# pandemic-v0001.net
KiCad netlist of a schematic drawn in EAGLE
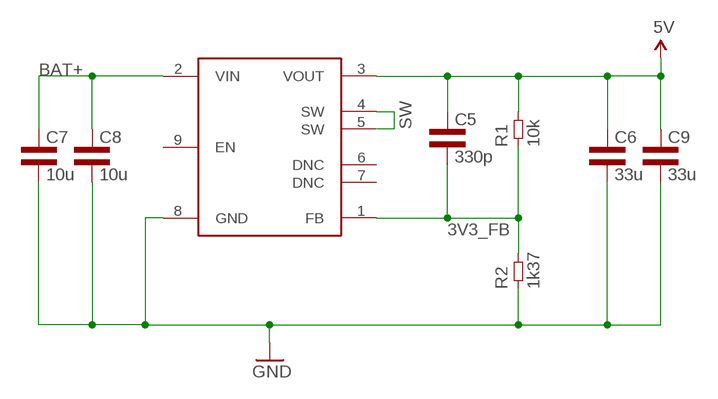
[diagram p0: schematic, sheet 1]
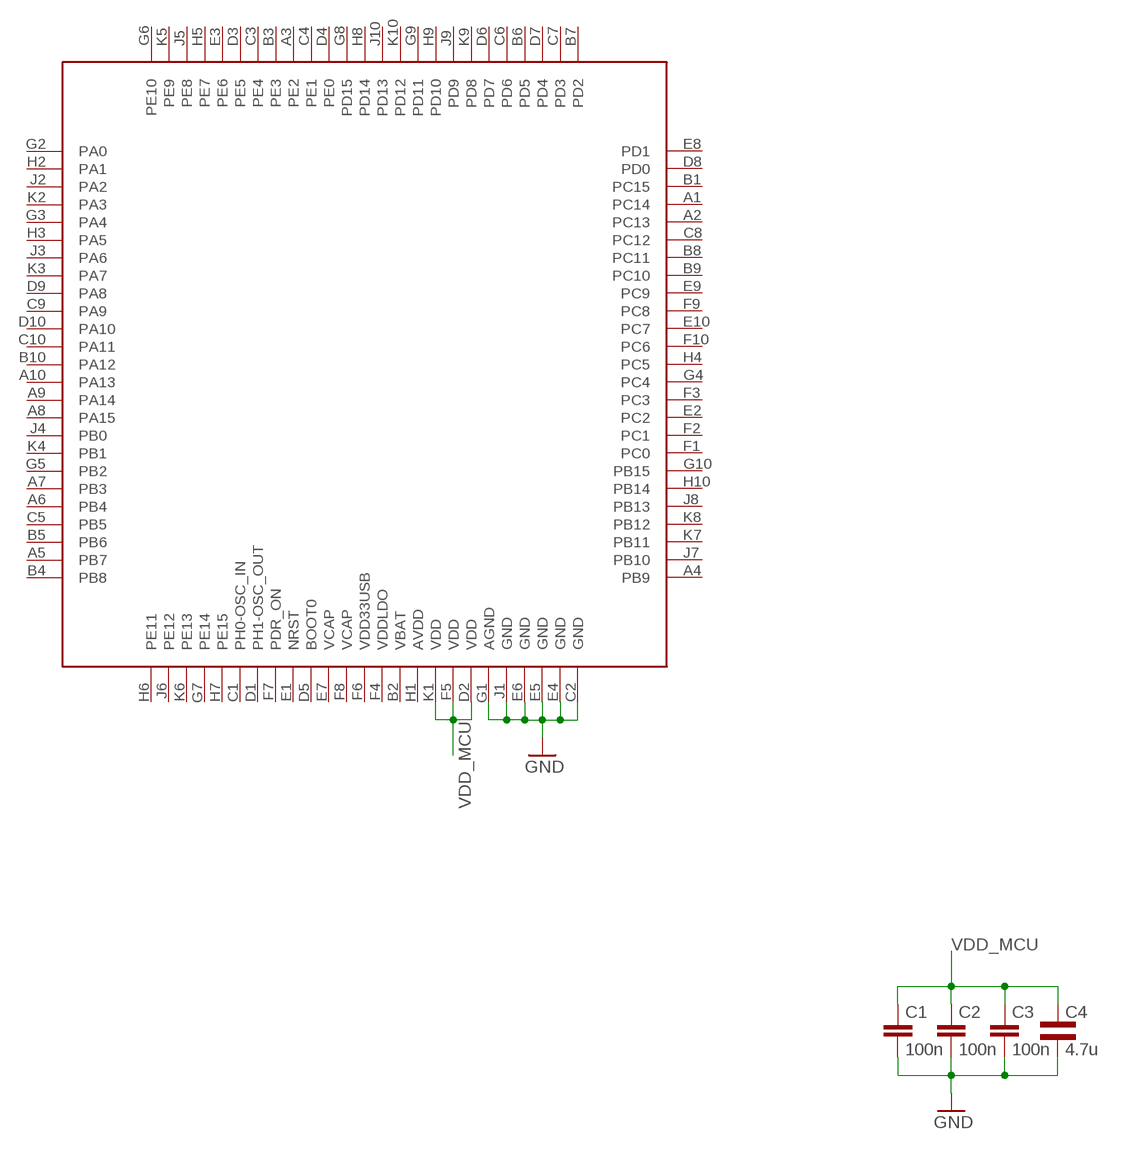
[diagram p1: schematic, sheet 2]

(export (version "E")
  (design (tool "Eeschema 10.0.6"))
  (components
    (comp (ref "C1")
      (value "100n")
      (footprint "eagle-import:C0201")
      (libsource (lib "eagle-import") (part "C-EUC0201"))
    )
    (comp (ref "C2")
      (value "100n")
      (footprint "eagle-import:C0201")
      (libsource (lib "eagle-import") (part "C-EUC0201"))
    )
    (comp (ref "C3")
      (value "100n")
      (footprint "eagle-import:C0201")
      (libsource (lib "eagle-import") (part "C-EUC0201"))
    )
    (comp (ref "C4")
      (value "4.7u")
      (footprint "eagle-import:0805L3")
      (libsource (lib "eagle-import") (part "CAP0805L3"))
    )
    (comp (ref "U1")
      (value "STM32H743VIH")
      (footprint "eagle-import:BGA100C80P10X10_800X800X110")
      (libsource (lib "eagle-import") (part "STM32H743VIH"))
    )
    (comp (ref "C5")
      (value "330p")
      (footprint "eagle-import:0402L3")
      (libsource (lib "eagle-import") (part "CAP0402L3"))
    )
    (comp (ref "C6")
      (value "33u")
      (footprint "eagle-import:1210L3")
      (libsource (lib "eagle-import") (part "CAP1210L3"))
    )
    (comp (ref "C7")
      (value "10u")
      (footprint "eagle-import:1210L3")
      (libsource (lib "eagle-import") (part "CAP1210L3"))
    )
    (comp (ref "C8")
      (value "10u")
      (footprint "eagle-import:1210L3")
      (libsource (lib "eagle-import") (part "CAP1210L3"))
    )
    (comp (ref "C9")
      (value "33u")
      (footprint "eagle-import:1210L3")
      (libsource (lib "eagle-import") (part "CAP1210L3"))
    )
    (comp (ref "R1")
      (value "10k")
      (footprint "eagle-import:0402L3")
      (libsource (lib "eagle-import") (part "RES0402L3"))
    )
    (comp (ref "R2")
      (value "1k37")
      (footprint "eagle-import:0402L3")
      (libsource (lib "eagle-import") (part "RES0402L3"))
    )
    (comp (ref "U2")
      (value "TPSM84209RKH")
      (footprint "eagle-import:TPSM84209RKHT")
      (libsource (lib "eagle-import") (part "TPSM84209RKH"))
    )
  )
  (nets
    (net (code "1") (name "3V3_FB") (class "Default")
      (node (ref "C5") (pin "P$2") (pinfunction "2_P$2") (pintype "bidirectional"))
      (node (ref "R1") (pin "P$1") (pinfunction "1_P$1") (pintype "bidirectional"))
      (node (ref "R2") (pin "P$2") (pinfunction "2_P$2") (pintype "bidirectional"))
      (node (ref "U2") (pin "1") (pinfunction "FB_1") (pintype "bidirectional"))
    )
    (net (code "2") (name "5V") (class "Default")
      (node (ref "C5") (pin "P$1") (pinfunction "1_P$1") (pintype "bidirectional"))
      (node (ref "C6") (pin "P$1") (pinfunction "1_P$1") (pintype "bidirectional"))
      (node (ref "C9") (pin "P$1") (pinfunction "1_P$1") (pintype "bidirectional"))
      (node (ref "R1") (pin "P$2") (pinfunction "2_P$2") (pintype "bidirectional"))
      (node (ref "U2") (pin "3") (pinfunction "VOUT_3") (pintype "bidirectional"))
    )
    (net (code "3") (name "BAT+") (class "Default")
      (node (ref "C7") (pin "P$1") (pinfunction "1_P$1") (pintype "bidirectional"))
      (node (ref "C8") (pin "P$1") (pinfunction "1_P$1") (pintype "bidirectional"))
      (node (ref "U2") (pin "2") (pinfunction "VIN_2") (pintype "bidirectional"))
    )
    (net (code "4") (name "GND") (class "Default")
      (node (ref "C1") (pin "2") (pinfunction "2_2") (pintype "passive"))
      (node (ref "C2") (pin "2") (pinfunction "2_2") (pintype "passive"))
      (node (ref "C3") (pin "2") (pinfunction "2_2") (pintype "passive"))
      (node (ref "C4") (pin "2") (pinfunction "2_2") (pintype "bidirectional"))
      (node (ref "C6") (pin "P$2") (pinfunction "2_P$2") (pintype "bidirectional"))
      (node (ref "C7") (pin "P$2") (pinfunction "2_P$2") (pintype "bidirectional"))
      (node (ref "C8") (pin "P$2") (pinfunction "2_P$2") (pintype "bidirectional"))
      (node (ref "C9") (pin "P$2") (pinfunction "2_P$2") (pintype "bidirectional"))
      (node (ref "R2") (pin "P$1") (pinfunction "1_P$1") (pintype "bidirectional"))
      (node (ref "U1") (pin "C2") (pinfunction "GND_C2") (pintype "bidirectional"))
      (node (ref "U1") (pin "E4") (pinfunction "GND_E4") (pintype "bidirectional"))
      (node (ref "U1") (pin "E5") (pinfunction "GND_E5") (pintype "bidirectional"))
      (node (ref "U1") (pin "E6") (pinfunction "GND_E6") (pintype "bidirectional"))
      (node (ref "U1") (pin "G1") (pinfunction "AGND_G1") (pintype "bidirectional"))
      (node (ref "U1") (pin "J1") (pinfunction "GND_J1") (pintype "bidirectional"))
      (node (ref "U2") (pin "8") (pinfunction "GND_8") (pintype "bidirectional"))
    )
    (net (code "5") (name "SW") (class "Default")
      (node (ref "U2") (pin "4") (pinfunction "SW_4") (pintype "bidirectional"))
      (node (ref "U2") (pin "5") (pinfunction "SW_5") (pintype "bidirectional"))
    )
    (net (code "6") (name "VDD_MCU") (class "Default")
      (node (ref "C1") (pin "1") (pinfunction "1_1") (pintype "passive"))
      (node (ref "C2") (pin "1") (pinfunction "1_1") (pintype "passive"))
      (node (ref "C3") (pin "1") (pinfunction "1_1") (pintype "passive"))
      (node (ref "C4") (pin "1") (pinfunction "1_1") (pintype "bidirectional"))
      (node (ref "U1") (pin "D2") (pinfunction "VDD_D2") (pintype "bidirectional"))
      (node (ref "U1") (pin "F5") (pinfunction "VDD_F5") (pintype "bidirectional"))
      (node (ref "U1") (pin "K1") (pinfunction "VDD_K1") (pintype "bidirectional"))
    )
    (net (code "7") (name "unconnected-(U1-AVDD-PadH1)") (class "Default")
      (node (ref "U1") (pin "H1") (pinfunction "AVDD_H1") (pintype "bidirectional"))
    )
    (net (code "8") (name "unconnected-(U1-BOOT0-PadD5)") (class "Default")
      (node (ref "U1") (pin "D5") (pinfunction "BOOT0_D5") (pintype "bidirectional"))
    )
    (net (code "9") (name "unconnected-(U1-NRST-PadE1)") (class "Default")
      (node (ref "U1") (pin "E1") (pinfunction "NRST_E1") (pintype "bidirectional"))
    )
    (net (code "10") (name "unconnected-(U1-PA0-PadG2)") (class "Default")
      (node (ref "U1") (pin "G2") (pinfunction "PA0_G2") (pintype "bidirectional"))
    )
    (net (code "11") (name "unconnected-(U1-PA1-PadH2)") (class "Default")
      (node (ref "U1") (pin "H2") (pinfunction "PA1_H2") (pintype "bidirectional"))
    )
    (net (code "12") (name "unconnected-(U1-PA2-PadJ2)") (class "Default")
      (node (ref "U1") (pin "J2") (pinfunction "PA2_J2") (pintype "bidirectional"))
    )
    (net (code "13") (name "unconnected-(U1-PA3-PadK2)") (class "Default")
      (node (ref "U1") (pin "K2") (pinfunction "PA3_K2") (pintype "bidirectional"))
    )
    (net (code "14") (name "unconnected-(U1-PA4-PadG3)") (class "Default")
      (node (ref "U1") (pin "G3") (pinfunction "PA4_G3") (pintype "bidirectional"))
    )
    (net (code "15") (name "unconnected-(U1-PA5-PadH3)") (class "Default")
      (node (ref "U1") (pin "H3") (pinfunction "PA5_H3") (pintype "bidirectional"))
    )
    (net (code "16") (name "unconnected-(U1-PA6-PadJ3)") (class "Default")
      (node (ref "U1") (pin "J3") (pinfunction "PA6_J3") (pintype "bidirectional"))
    )
    (net (code "17") (name "unconnected-(U1-PA7-PadK3)") (class "Default")
      (node (ref "U1") (pin "K3") (pinfunction "PA7_K3") (pintype "bidirectional"))
    )
    (net (code "18") (name "unconnected-(U1-PA8-PadD9)") (class "Default")
      (node (ref "U1") (pin "D9") (pinfunction "PA8_D9") (pintype "bidirectional"))
    )
    (net (code "19") (name "unconnected-(U1-PA9-PadC9)") (class "Default")
      (node (ref "U1") (pin "C9") (pinfunction "PA9_C9") (pintype "bidirectional"))
    )
    (net (code "20") (name "unconnected-(U1-PA10-PadD10)") (class "Default")
      (node (ref "U1") (pin "D10") (pinfunction "PA10_D10") (pintype "bidirectional"))
    )
    (net (code "21") (name "unconnected-(U1-PA11-PadC10)") (class "Default")
      (node (ref "U1") (pin "C10") (pinfunction "PA11_C10") (pintype "bidirectional"))
    )
    (net (code "22") (name "unconnected-(U1-PA12-PadB10)") (class "Default")
      (node (ref "U1") (pin "B10") (pinfunction "PA12_B10") (pintype "bidirectional"))
    )
    (net (code "23") (name "unconnected-(U1-PA13-PadA10)") (class "Default")
      (node (ref "U1") (pin "A10") (pinfunction "PA13_A10") (pintype "bidirectional"))
    )
    (net (code "24") (name "unconnected-(U1-PA14-PadA9)") (class "Default")
      (node (ref "U1") (pin "A9") (pinfunction "PA14_A9") (pintype "bidirectional"))
    )
    (net (code "25") (name "unconnected-(U1-PA15-PadA8)") (class "Default")
      (node (ref "U1") (pin "A8") (pinfunction "PA15_A8") (pintype "bidirectional"))
    )
    (net (code "26") (name "unconnected-(U1-PB0-PadJ4)") (class "Default")
      (node (ref "U1") (pin "J4") (pinfunction "PB0_J4") (pintype "bidirectional"))
    )
    (net (code "27") (name "unconnected-(U1-PB1-PadK4)") (class "Default")
      (node (ref "U1") (pin "K4") (pinfunction "PB1_K4") (pintype "bidirectional"))
    )
    (net (code "28") (name "unconnected-(U1-PB2-PadG5)") (class "Default")
      (node (ref "U1") (pin "G5") (pinfunction "PB2_G5") (pintype "bidirectional"))
    )
    (net (code "29") (name "unconnected-(U1-PB3-PadA7)") (class "Default")
      (node (ref "U1") (pin "A7") (pinfunction "PB3_A7") (pintype "bidirectional"))
    )
    (net (code "30") (name "unconnected-(U1-PB4-PadA6)") (class "Default")
      (node (ref "U1") (pin "A6") (pinfunction "PB4_A6") (pintype "bidirectional"))
    )
    (net (code "31") (name "unconnected-(U1-PB5-PadC5)") (class "Default")
      (node (ref "U1") (pin "C5") (pinfunction "PB5_C5") (pintype "bidirectional"))
    )
    (net (code "32") (name "unconnected-(U1-PB6-PadB5)") (class "Default")
      (node (ref "U1") (pin "B5") (pinfunction "PB6_B5") (pintype "bidirectional"))
    )
    (net (code "33") (name "unconnected-(U1-PB7-PadA5)") (class "Default")
      (node (ref "U1") (pin "A5") (pinfunction "PB7_A5") (pintype "bidirectional"))
    )
    (net (code "34") (name "unconnected-(U1-PB8-PadB4)") (class "Default")
      (node (ref "U1") (pin "B4") (pinfunction "PB8_B4") (pintype "bidirectional"))
    )
    (net (code "35") (name "unconnected-(U1-PB9-PadA4)") (class "Default")
      (node (ref "U1") (pin "A4") (pinfunction "PB9_A4") (pintype "bidirectional"))
    )
    (net (code "36") (name "unconnected-(U1-PB10-PadJ7)") (class "Default")
      (node (ref "U1") (pin "J7") (pinfunction "PB10_J7") (pintype "bidirectional"))
    )
    (net (code "37") (name "unconnected-(U1-PB11-PadK7)") (class "Default")
      (node (ref "U1") (pin "K7") (pinfunction "PB11_K7") (pintype "bidirectional"))
    )
    (net (code "38") (name "unconnected-(U1-PB12-PadK8)") (class "Default")
      (node (ref "U1") (pin "K8") (pinfunction "PB12_K8") (pintype "bidirectional"))
    )
    (net (code "39") (name "unconnected-(U1-PB13-PadJ8)") (class "Default")
      (node (ref "U1") (pin "J8") (pinfunction "PB13_J8") (pintype "bidirectional"))
    )
    (net (code "40") (name "unconnected-(U1-PB14-PadH10)") (class "Default")
      (node (ref "U1") (pin "H10") (pinfunction "PB14_H10") (pintype "bidirectional"))
    )
    (net (code "41") (name "unconnected-(U1-PB15-PadG10)") (class "Default")
      (node (ref "U1") (pin "G10") (pinfunction "PB15_G10") (pintype "bidirectional"))
    )
    (net (code "42") (name "unconnected-(U1-PC0-PadF1)") (class "Default")
      (node (ref "U1") (pin "F1") (pinfunction "PC0_F1") (pintype "bidirectional"))
    )
    (net (code "43") (name "unconnected-(U1-PC1-PadF2)") (class "Default")
      (node (ref "U1") (pin "F2") (pinfunction "PC1_F2") (pintype "bidirectional"))
    )
    (net (code "44") (name "unconnected-(U1-PC2-PadE2)") (class "Default")
      (node (ref "U1") (pin "E2") (pinfunction "PC2_E2") (pintype "bidirectional"))
    )
    (net (code "45") (name "unconnected-(U1-PC3-PadF3)") (class "Default")
      (node (ref "U1") (pin "F3") (pinfunction "PC3_F3") (pintype "bidirectional"))
    )
    (net (code "46") (name "unconnected-(U1-PC4-PadG4)") (class "Default")
      (node (ref "U1") (pin "G4") (pinfunction "PC4_G4") (pintype "bidirectional"))
    )
    (net (code "47") (name "unconnected-(U1-PC5-PadH4)") (class "Default")
      (node (ref "U1") (pin "H4") (pinfunction "PC5_H4") (pintype "bidirectional"))
    )
    (net (code "48") (name "unconnected-(U1-PC6-PadF10)") (class "Default")
      (node (ref "U1") (pin "F10") (pinfunction "PC6_F10") (pintype "bidirectional"))
    )
    (net (code "49") (name "unconnected-(U1-PC7-PadE10)") (class "Default")
      (node (ref "U1") (pin "E10") (pinfunction "PC7_E10") (pintype "bidirectional"))
    )
    (net (code "50") (name "unconnected-(U1-PC8-PadF9)") (class "Default")
      (node (ref "U1") (pin "F9") (pinfunction "PC8_F9") (pintype "bidirectional"))
    )
    (net (code "51") (name "unconnected-(U1-PC9-PadE9)") (class "Default")
      (node (ref "U1") (pin "E9") (pinfunction "PC9_E9") (pintype "bidirectional"))
    )
    (net (code "52") (name "unconnected-(U1-PC10-PadB9)") (class "Default")
      (node (ref "U1") (pin "B9") (pinfunction "PC10_B9") (pintype "bidirectional"))
    )
    (net (code "53") (name "unconnected-(U1-PC11-PadB8)") (class "Default")
      (node (ref "U1") (pin "B8") (pinfunction "PC11_B8") (pintype "bidirectional"))
    )
    (net (code "54") (name "unconnected-(U1-PC12-PadC8)") (class "Default")
      (node (ref "U1") (pin "C8") (pinfunction "PC12_C8") (pintype "bidirectional"))
    )
    (net (code "55") (name "unconnected-(U1-PC13-PadA2)") (class "Default")
      (node (ref "U1") (pin "A2") (pinfunction "PC13_A2") (pintype "bidirectional"))
    )
    (net (code "56") (name "unconnected-(U1-PC14-PadA1)") (class "Default")
      (node (ref "U1") (pin "A1") (pinfunction "PC14_A1") (pintype "bidirectional"))
    )
    (net (code "57") (name "unconnected-(U1-PC15-PadB1)") (class "Default")
      (node (ref "U1") (pin "B1") (pinfunction "PC15_B1") (pintype "bidirectional"))
    )
    (net (code "58") (name "unconnected-(U1-PD0-PadD8)") (class "Default")
      (node (ref "U1") (pin "D8") (pinfunction "PD0_D8") (pintype "bidirectional"))
    )
    (net (code "59") (name "unconnected-(U1-PD1-PadE8)") (class "Default")
      (node (ref "U1") (pin "E8") (pinfunction "PD1_E8") (pintype "bidirectional"))
    )
    (net (code "60") (name "unconnected-(U1-PD2-PadB7)") (class "Default")
      (node (ref "U1") (pin "B7") (pinfunction "PD2_B7") (pintype "bidirectional"))
    )
    (net (code "61") (name "unconnected-(U1-PD3-PadC7)") (class "Default")
      (node (ref "U1") (pin "C7") (pinfunction "PD3_C7") (pintype "bidirectional"))
    )
    (net (code "62") (name "unconnected-(U1-PD4-PadD7)") (class "Default")
      (node (ref "U1") (pin "D7") (pinfunction "PD4_D7") (pintype "bidirectional"))
    )
    (net (code "63") (name "unconnected-(U1-PD5-PadB6)") (class "Default")
      (node (ref "U1") (pin "B6") (pinfunction "PD5_B6") (pintype "bidirectional"))
    )
    (net (code "64") (name "unconnected-(U1-PD6-PadC6)") (class "Default")
      (node (ref "U1") (pin "C6") (pinfunction "PD6_C6") (pintype "bidirectional"))
    )
    (net (code "65") (name "unconnected-(U1-PD7-PadD6)") (class "Default")
      (node (ref "U1") (pin "D6") (pinfunction "PD7_D6") (pintype "bidirectional"))
    )
    (net (code "66") (name "unconnected-(U1-PD8-PadK9)") (class "Default")
      (node (ref "U1") (pin "K9") (pinfunction "PD8_K9") (pintype "bidirectional"))
    )
    (net (code "67") (name "unconnected-(U1-PD9-PadJ9)") (class "Default")
      (node (ref "U1") (pin "J9") (pinfunction "PD9_J9") (pintype "bidirectional"))
    )
    (net (code "68") (name "unconnected-(U1-PD10-PadH9)") (class "Default")
      (node (ref "U1") (pin "H9") (pinfunction "PD10_H9") (pintype "bidirectional"))
    )
    (net (code "69") (name "unconnected-(U1-PD11-PadG9)") (class "Default")
      (node (ref "U1") (pin "G9") (pinfunction "PD11_G9") (pintype "bidirectional"))
    )
    (net (code "70") (name "unconnected-(U1-PD12-PadK10)") (class "Default")
      (node (ref "U1") (pin "K10") (pinfunction "PD12_K10") (pintype "bidirectional"))
    )
    (net (code "71") (name "unconnected-(U1-PD13-PadJ10)") (class "Default")
      (node (ref "U1") (pin "J10") (pinfunction "PD13_J10") (pintype "bidirectional"))
    )
    (net (code "72") (name "unconnected-(U1-PD14-PadH8)") (class "Default")
      (node (ref "U1") (pin "H8") (pinfunction "PD14_H8") (pintype "bidirectional"))
    )
    (net (code "73") (name "unconnected-(U1-PD15-PadG8)") (class "Default")
      (node (ref "U1") (pin "G8") (pinfunction "PD15_G8") (pintype "bidirectional"))
    )
    (net (code "74") (name "unconnected-(U1-PDR_ON-PadF7)") (class "Default")
      (node (ref "U1") (pin "F7") (pinfunction "PDR_ON_F7") (pintype "bidirectional"))
    )
    (net (code "75") (name "unconnected-(U1-PE0-PadD4)") (class "Default")
      (node (ref "U1") (pin "D4") (pinfunction "PE0_D4") (pintype "bidirectional"))
    )
    (net (code "76") (name "unconnected-(U1-PE1-PadC4)") (class "Default")
      (node (ref "U1") (pin "C4") (pinfunction "PE1_C4") (pintype "bidirectional"))
    )
    (net (code "77") (name "unconnected-(U1-PE2-PadA3)") (class "Default")
      (node (ref "U1") (pin "A3") (pinfunction "PE2_A3") (pintype "bidirectional"))
    )
    (net (code "78") (name "unconnected-(U1-PE3-PadB3)") (class "Default")
      (node (ref "U1") (pin "B3") (pinfunction "PE3_B3") (pintype "bidirectional"))
    )
    (net (code "79") (name "unconnected-(U1-PE4-PadC3)") (class "Default")
      (node (ref "U1") (pin "C3") (pinfunction "PE4_C3") (pintype "bidirectional"))
    )
    (net (code "80") (name "unconnected-(U1-PE5-PadD3)") (class "Default")
      (node (ref "U1") (pin "D3") (pinfunction "PE5_D3") (pintype "bidirectional"))
    )
    (net (code "81") (name "unconnected-(U1-PE6-PadE3)") (class "Default")
      (node (ref "U1") (pin "E3") (pinfunction "PE6_E3") (pintype "bidirectional"))
    )
    (net (code "82") (name "unconnected-(U1-PE7-PadH5)") (class "Default")
      (node (ref "U1") (pin "H5") (pinfunction "PE7_H5") (pintype "bidirectional"))
    )
    (net (code "83") (name "unconnected-(U1-PE8-PadJ5)") (class "Default")
      (node (ref "U1") (pin "J5") (pinfunction "PE8_J5") (pintype "bidirectional"))
    )
    (net (code "84") (name "unconnected-(U1-PE9-PadK5)") (class "Default")
      (node (ref "U1") (pin "K5") (pinfunction "PE9_K5") (pintype "bidirectional"))
    )
    (net (code "85") (name "unconnected-(U1-PE10-PadG6)") (class "Default")
      (node (ref "U1") (pin "G6") (pinfunction "PE10_G6") (pintype "bidirectional"))
    )
    (net (code "86") (name "unconnected-(U1-PE11-PadH6)") (class "Default")
      (node (ref "U1") (pin "H6") (pinfunction "PE11_H6") (pintype "bidirectional"))
    )
    (net (code "87") (name "unconnected-(U1-PE12-PadJ6)") (class "Default")
      (node (ref "U1") (pin "J6") (pinfunction "PE12_J6") (pintype "bidirectional"))
    )
    (net (code "88") (name "unconnected-(U1-PE13-PadK6)") (class "Default")
      (node (ref "U1") (pin "K6") (pinfunction "PE13_K6") (pintype "bidirectional"))
    )
    (net (code "89") (name "unconnected-(U1-PE14-PadG7)") (class "Default")
      (node (ref "U1") (pin "G7") (pinfunction "PE14_G7") (pintype "bidirectional"))
    )
    (net (code "90") (name "unconnected-(U1-PE15-PadH7)") (class "Default")
      (node (ref "U1") (pin "H7") (pinfunction "PE15_H7") (pintype "bidirectional"))
    )
    (net (code "91") (name "unconnected-(U1-PH0-OSC_IN-PadC1)") (class "Default")
      (node (ref "U1") (pin "C1") (pinfunction "PH0-OSC_IN_C1") (pintype "bidirectional"))
    )
    (net (code "92") (name "unconnected-(U1-PH1-OSC_OUT-PadD1)") (class "Default")
      (node (ref "U1") (pin "D1") (pinfunction "PH1-OSC_OUT_D1") (pintype "bidirectional"))
    )
    (net (code "93") (name "unconnected-(U1-VBAT-PadB2)") (class "Default")
      (node (ref "U1") (pin "B2") (pinfunction "VBAT_B2") (pintype "bidirectional"))
    )
    (net (code "94") (name "unconnected-(U1-VCAP-PadE7)") (class "Default")
      (node (ref "U1") (pin "E7") (pinfunction "VCAP_E7") (pintype "bidirectional"))
    )
    (net (code "95") (name "unconnected-(U1-VCAP-PadF8)") (class "Default")
      (node (ref "U1") (pin "F8") (pinfunction "VCAP_F8") (pintype "bidirectional"))
    )
    (net (code "96") (name "unconnected-(U1-VDD33USB-PadF6)") (class "Default")
      (node (ref "U1") (pin "F6") (pinfunction "VDD33USB_F6") (pintype "bidirectional"))
    )
    (net (code "97") (name "unconnected-(U1-VDDLDO-PadF4)") (class "Default")
      (node (ref "U1") (pin "F4") (pinfunction "VDDLDO_F4") (pintype "bidirectional"))
    )
    (net (code "98") (name "unconnected-(U2-DNC-Pad6)") (class "Default")
      (node (ref "U2") (pin "6") (pinfunction "DNC_6") (pintype "bidirectional"))
    )
    (net (code "99") (name "unconnected-(U2-DNC-Pad7)") (class "Default")
      (node (ref "U2") (pin "7") (pinfunction "DNC_7") (pintype "bidirectional"))
    )
    (net (code "100") (name "unconnected-(U2-EN-Pad9)") (class "Default")
      (node (ref "U2") (pin "9") (pinfunction "EN_9") (pintype "bidirectional"))
    )
  )
)
